# SAFE-MSP.net
KiCad netlist of a schematic drawn in EAGLE
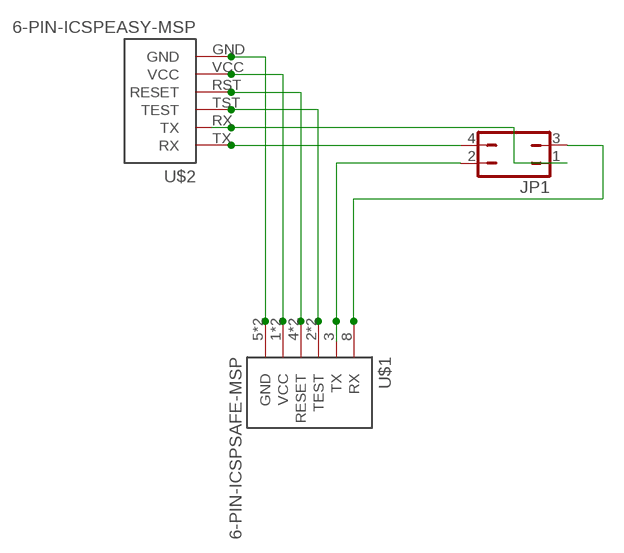
[diagram p0: schematic, sheet 1]

(export (version "E")
  (design (tool "Eeschema 10.0.6"))
  (components
    (comp (ref "JP1")
      (value "JP2Q")
      (footprint "eagle-import:JP2Q")
      (libsource (lib "eagle-import") (part "JP2Q"))
    )
    (comp (ref "U$1")
      (value "6-PIN-ICSPSAFE-MSP")
      (footprint "eagle-import:SAFEMSP")
      (libsource (lib "eagle-import") (part "6-PIN-ICSPSAFE-MSP"))
    )
    (comp (ref "U$2")
      (value "6-PIN-ICSPEASY-MSP")
      (footprint "eagle-import:EASYMSP-6PIN")
      (libsource (lib "eagle-import") (part "6-PIN-ICSPEASY-MSP"))
    )
  )
  (nets
    (net (code "1") (name "Net-(U$1-GND-Pad10)") (class "Default")
      (node (ref "U$1") (pin "10") (pinfunction "GND_10") (pintype "bidirectional"))
      (node (ref "U$1") (pin "5") (pinfunction "GND_5") (pintype "bidirectional"))
      (node (ref "U$2") (pin "GND") (pinfunction "GND_GND") (pintype "bidirectional"))
    )
    (net (code "2") (name "Net-(U$1-RX)") (class "Default")
      (node (ref "JP1") (pin "3") (pinfunction "3_3") (pintype "passive"))
      (node (ref "U$1") (pin "8") (pinfunction "RX_8") (pintype "bidirectional"))
    )
    (net (code "3") (name "Net-(U$1-TX)") (class "Default")
      (node (ref "JP1") (pin "2") (pinfunction "2_2") (pintype "passive"))
      (node (ref "U$1") (pin "3") (pinfunction "TX_3") (pintype "bidirectional"))
    )
    (net (code "4") (name "Net-(U$1-VCC-Pad1)") (class "Default")
      (node (ref "U$1") (pin "1") (pinfunction "VCC_1") (pintype "bidirectional"))
      (node (ref "U$1") (pin "6") (pinfunction "VCC_6") (pintype "bidirectional"))
      (node (ref "U$2") (pin "VCC") (pinfunction "VCC_VCC") (pintype "bidirectional"))
    )
    (net (code "5") (name "Net-(U$2-RESET)") (class "Default")
      (node (ref "U$1") (pin "4") (pinfunction "RESET_4") (pintype "bidirectional"))
      (node (ref "U$1") (pin "9") (pinfunction "RESET_9") (pintype "bidirectional"))
      (node (ref "U$2") (pin "RST") (pinfunction "RESET_RST") (pintype "bidirectional"))
    )
    (net (code "6") (name "Net-(U$2-RX)") (class "Default")
      (node (ref "JP1") (pin "4") (pinfunction "4_4") (pintype "passive"))
      (node (ref "U$2") (pin "TX") (pinfunction "RX_TX") (pintype "bidirectional"))
    )
    (net (code "7") (name "Net-(U$2-TEST)") (class "Default")
      (node (ref "U$1") (pin "2") (pinfunction "TEST_2") (pintype "bidirectional"))
      (node (ref "U$1") (pin "7") (pinfunction "TEST_7") (pintype "bidirectional"))
      (node (ref "U$2") (pin "TST") (pinfunction "TEST_TST") (pintype "bidirectional"))
    )
    (net (code "8") (name "Net-(U$2-TX)") (class "Default")
      (node (ref "JP1") (pin "1") (pinfunction "1_1") (pintype "passive"))
      (node (ref "U$2") (pin "RX") (pinfunction "TX_RX") (pintype "bidirectional"))
    )
  )
)
